# DA_CNNC.net
KiCad netlist of a schematic drawn in EasyEDA Pro
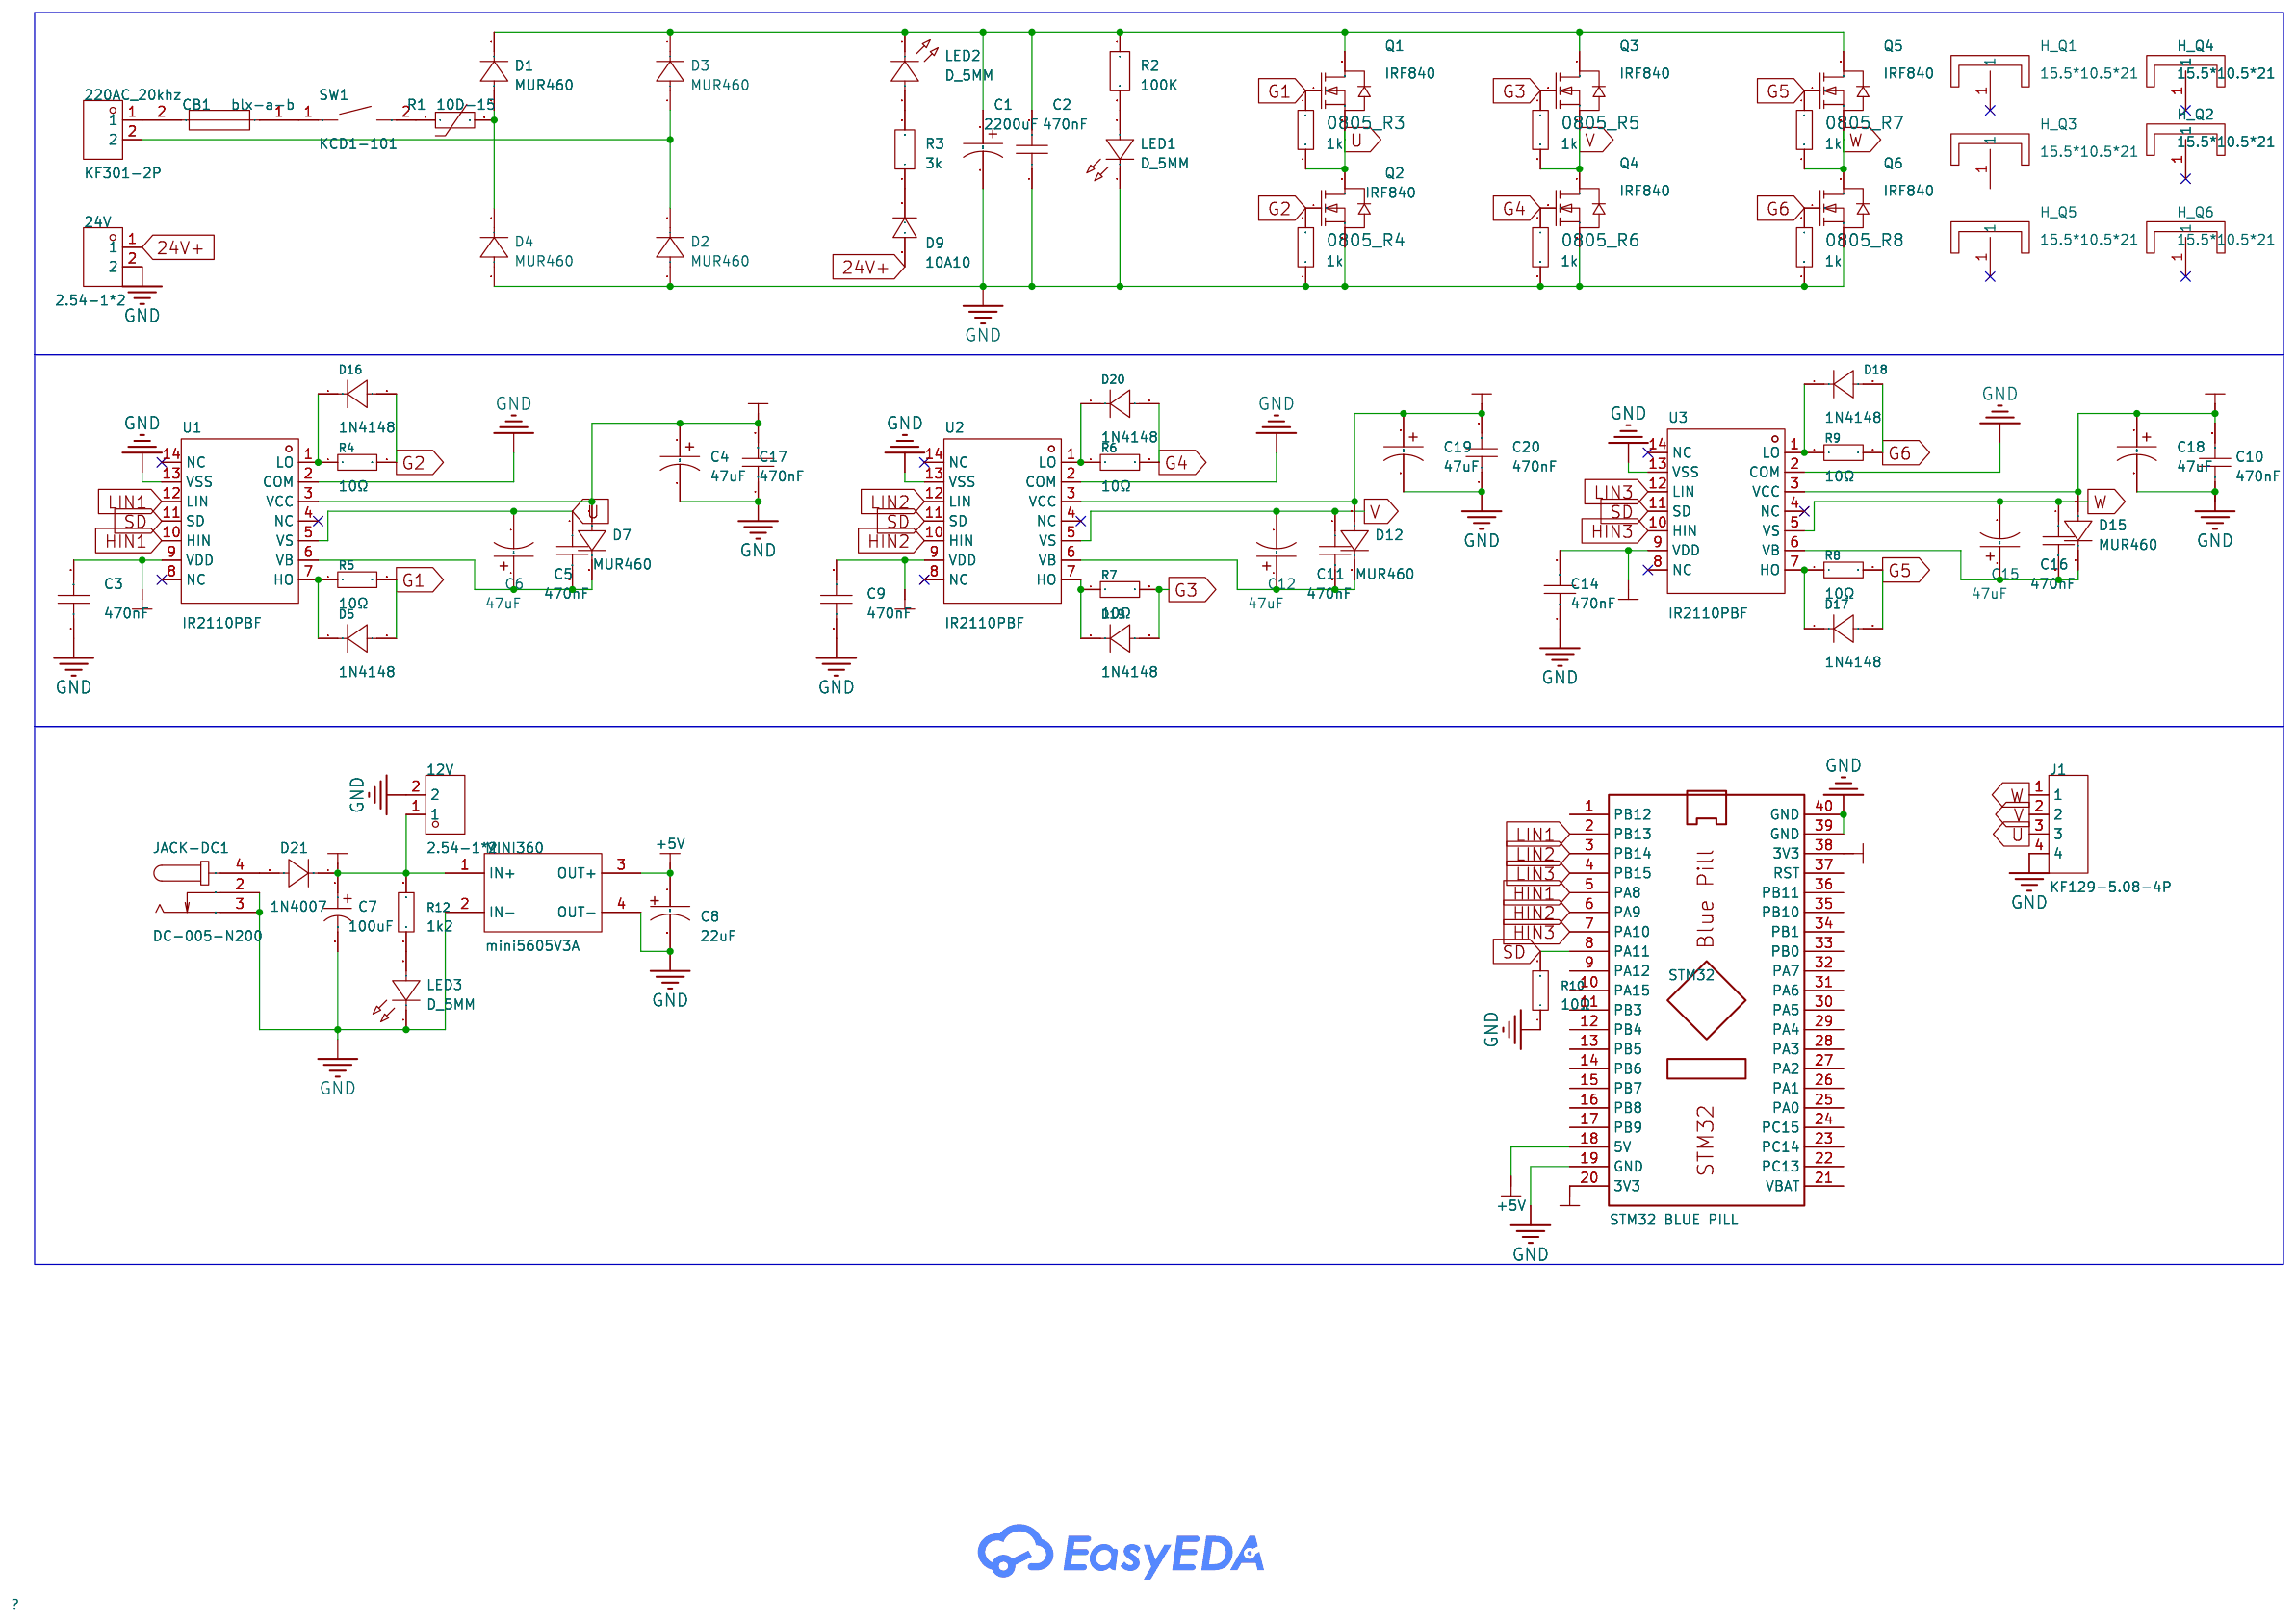
[diagram p0: schematic sheet]

(export (version "E")
  (design (tool "Eeschema 10.0.6"))
  (components
    (comp (ref "12V")
      (value "2.54-1*2")
      (footprint "easyedapro:HDR-TH_2P-P2.54-V-M")
      (fields (field (name "Manufacturer") "ZHOURI(洲日)"))
      (libsource (lib "easyedapro") (part "2.54-1*2"))
    )
    (comp (ref "24V")
      (value "2.54-1*2")
      (footprint "easyedapro:HDR-TH_2P-P2.54-V-M")
      (fields (field (name "Manufacturer") "ZHOURI(洲日)"))
      (libsource (lib "easyedapro") (part "2.54-1*2"))
    )
    (comp (ref "220AC_20khz")
      (value "KF301-2P")
      (footprint "easyedapro:CONN-TH_XY301V-A-5.0-2P")
      (libsource (lib "easyedapro") (part "KF301-2P接线端子"))
    )
    (comp (ref "0805_R3")
      (value "1k")
      (footprint "easyedapro:R0805")
      (fields
        (field (name "Manufacturer Part") "0805W8F1502T5E")
        (field (name "Manufacturer") "UNI-ROYAL(厚声)")
      )
      (libsource (lib "easyedapro") (part "0805W8F1502T5E"))
    )
    (comp (ref "0805_R4")
      (value "1k")
      (footprint "easyedapro:R0805")
      (fields
        (field (name "Manufacturer Part") "0805W8F1502T5E")
        (field (name "Manufacturer") "UNI-ROYAL(厚声)")
      )
      (libsource (lib "easyedapro") (part "0805W8F1502T5E"))
    )
    (comp (ref "0805_R5")
      (value "1k")
      (footprint "easyedapro:R0805")
      (fields
        (field (name "Manufacturer Part") "0805W8F1502T5E")
        (field (name "Manufacturer") "UNI-ROYAL(厚声)")
      )
      (libsource (lib "easyedapro") (part "0805W8F1502T5E"))
    )
    (comp (ref "0805_R6")
      (value "1k")
      (footprint "easyedapro:R0805")
      (fields
        (field (name "Manufacturer Part") "0805W8F1502T5E")
        (field (name "Manufacturer") "UNI-ROYAL(厚声)")
      )
      (libsource (lib "easyedapro") (part "0805W8F1502T5E"))
    )
    (comp (ref "0805_R7")
      (value "1k")
      (footprint "easyedapro:R0805")
      (fields
        (field (name "Manufacturer Part") "0805W8F1502T5E")
        (field (name "Manufacturer") "UNI-ROYAL(厚声)")
      )
      (libsource (lib "easyedapro") (part "0805W8F1502T5E"))
    )
    (comp (ref "0805_R8")
      (value "1k")
      (footprint "easyedapro:R0805")
      (fields
        (field (name "Manufacturer Part") "0805W8F1502T5E")
        (field (name "Manufacturer") "UNI-ROYAL(厚声)")
      )
      (libsource (lib "easyedapro") (part "0805W8F1502T5E"))
    )
    (comp (ref "C1")
      (value "2200uF")
      (footprint "easyedapro:CAP-TH_BD25.0-P10.00-D2.3-FD")
      (fields
        (field (name "Manufacturer Part") "450VXG220MEFCSN25X40")
        (field (name "Manufacturer") "Rubycon(红宝石)")
      )
      (libsource (lib "easyedapro") (part "450VXG220MEFCSN25X40"))
    )
    (comp (ref "C2")
      (value "470nF")
      (footprint "easyedapro:CAP-TH_L22.5-W7.5-P20.00-D1.2")
      (fields (field (name "Manufacturer Part") "KP474J2J2001") (field (name "Manufacturer") "KYET(科雅)"))
      (libsource (lib "easyedapro") (part "KP474J2J2001"))
    )
    (comp (ref "C3")
      (value "470nF")
      (footprint "easyedapro:C0805")
      (description "Capacitance:4.7pF Voltage Rating:100V Temperature Coefficient:NP0")
      (fields
        (field (name "Manufacturer Part") "CC0805CRNPO0BN4R7")
        (field (name "Manufacturer") "YAGEO(国巨)")
      )
      (libsource (lib "easyedapro") (part "CC0805CRNPO0BN4R7"))
    )
    (comp (ref "C4")
      (value "47uF")
      (footprint "easyedapro:CAP-TH_BD6.3-P2.5-D0.5")
      (fields (field (name "Manufacturer Part") "50V47uF CD288") (field (name "Manufacturer") "HRK(鸿瑞凯电子)"))
      (libsource (lib "easyedapro") (part "50V47UF CD288"))
    )
    (comp (ref "C5")
      (value "470nF")
      (footprint "easyedapro:C0805")
      (description "Capacitance:4.7pF Voltage Rating:100V Temperature Coefficient:NP0")
      (fields
        (field (name "Manufacturer Part") "CC0805CRNPO0BN4R7")
        (field (name "Manufacturer") "YAGEO(国巨)")
      )
      (libsource (lib "easyedapro") (part "CC0805CRNPO0BN4R7"))
    )
    (comp (ref "C6")
      (value "47uF")
      (footprint "easyedapro:CAP-TH_BD6.3-P2.5-D0.5")
      (fields (field (name "Manufacturer Part") "50V47uF CD288") (field (name "Manufacturer") "HRK(鸿瑞凯电子)"))
      (libsource (lib "easyedapro") (part "50V47UF CD288"))
    )
    (comp (ref "C7")
      (value "100uF")
      (footprint "easyedapro:CAP-TH_BD6.3-P2.50-D0.5-FD-100UF25V6.3X11KM")
      (fields
        (field (name "Manufacturer Part") "100uF25V6.3x11KM")
        (field (name "Manufacturer") "Econd(米朗电子)")
      )
      (libsource (lib "easyedapro") (part "100UF25V6.3X11KM"))
    )
    (comp (ref "C8")
      (value "22uF")
      (footprint "easyedapro:CAP-TH_BD4.0-P1.50-D0.8-FD")
      (fields (field (name "Manufacturer Part") "ECEA1CKA220") (field (name "Manufacturer") "PANASONIC(松下)"))
      (libsource (lib "easyedapro") (part "ECEA1CKA220"))
    )
    (comp (ref "C9")
      (value "470nF")
      (footprint "easyedapro:C0805")
      (description "Capacitance:4.7pF Voltage Rating:100V Temperature Coefficient:NP0")
      (fields
        (field (name "Manufacturer Part") "CC0805CRNPO0BN4R7")
        (field (name "Manufacturer") "YAGEO(国巨)")
      )
      (libsource (lib "easyedapro") (part "CC0805CRNPO0BN4R7"))
    )
    (comp (ref "C10")
      (value "470nF")
      (footprint "easyedapro:C0805")
      (description "Capacitance:4.7pF Voltage Rating:100V Temperature Coefficient:NP0")
      (fields
        (field (name "Manufacturer Part") "CC0805CRNPO0BN4R7")
        (field (name "Manufacturer") "YAGEO(国巨)")
      )
      (libsource (lib "easyedapro") (part "CC0805CRNPO0BN4R7"))
    )
    (comp (ref "C11")
      (value "470nF")
      (footprint "easyedapro:C0805")
      (description "Capacitance:4.7pF Voltage Rating:100V Temperature Coefficient:NP0")
      (fields
        (field (name "Manufacturer Part") "CC0805CRNPO0BN4R7")
        (field (name "Manufacturer") "YAGEO(国巨)")
      )
      (libsource (lib "easyedapro") (part "CC0805CRNPO0BN4R7"))
    )
    (comp (ref "C12")
      (value "47uF")
      (footprint "easyedapro:CAP-TH_BD6.3-P2.5-D0.5")
      (fields (field (name "Manufacturer Part") "50V47uF CD288") (field (name "Manufacturer") "HRK(鸿瑞凯电子)"))
      (libsource (lib "easyedapro") (part "50V47UF CD288"))
    )
    (comp (ref "C14")
      (value "470nF")
      (footprint "easyedapro:C0805")
      (description "Capacitance:4.7pF Voltage Rating:100V Temperature Coefficient:NP0")
      (fields
        (field (name "Manufacturer Part") "CC0805CRNPO0BN4R7")
        (field (name "Manufacturer") "YAGEO(国巨)")
      )
      (libsource (lib "easyedapro") (part "CC0805CRNPO0BN4R7"))
    )
    (comp (ref "C15")
      (value "47uF")
      (footprint "easyedapro:CAP-TH_BD6.3-P2.5-D0.5")
      (fields (field (name "Manufacturer Part") "50V47uF CD288") (field (name "Manufacturer") "HRK(鸿瑞凯电子)"))
      (libsource (lib "easyedapro") (part "50V47UF CD288"))
    )
    (comp (ref "C16")
      (value "470nF")
      (footprint "easyedapro:C0805")
      (description "Capacitance:4.7pF Voltage Rating:100V Temperature Coefficient:NP0")
      (fields
        (field (name "Manufacturer Part") "CC0805CRNPO0BN4R7")
        (field (name "Manufacturer") "YAGEO(国巨)")
      )
      (libsource (lib "easyedapro") (part "CC0805CRNPO0BN4R7"))
    )
    (comp (ref "C17")
      (value "470nF")
      (footprint "easyedapro:C0805")
      (description "Capacitance:4.7pF Voltage Rating:100V Temperature Coefficient:NP0")
      (fields
        (field (name "Manufacturer Part") "CC0805CRNPO0BN4R7")
        (field (name "Manufacturer") "YAGEO(国巨)")
      )
      (libsource (lib "easyedapro") (part "CC0805CRNPO0BN4R7"))
    )
    (comp (ref "C18")
      (value "47uF")
      (footprint "easyedapro:CAP-TH_BD6.3-P2.5-D0.5")
      (fields (field (name "Manufacturer Part") "50V47uF CD288") (field (name "Manufacturer") "HRK(鸿瑞凯电子)"))
      (libsource (lib "easyedapro") (part "50V47UF CD288"))
    )
    (comp (ref "C19")
      (value "47uF")
      (footprint "easyedapro:CAP-TH_BD6.3-P2.5-D0.5")
      (fields (field (name "Manufacturer Part") "50V47uF CD288") (field (name "Manufacturer") "HRK(鸿瑞凯电子)"))
      (libsource (lib "easyedapro") (part "50V47UF CD288"))
    )
    (comp (ref "C20")
      (value "470nF")
      (footprint "easyedapro:C0805")
      (description "Capacitance:4.7pF Voltage Rating:100V Temperature Coefficient:NP0")
      (fields
        (field (name "Manufacturer Part") "CC0805CRNPO0BN4R7")
        (field (name "Manufacturer") "YAGEO(国巨)")
      )
      (libsource (lib "easyedapro") (part "CC0805CRNPO0BN4R7"))
    )
    (comp (ref "CB1")
      (value "blx-a-b")
      (footprint "easyedapro:FUSE-TH_BLX-A-B")
      (description "Voltage Rating:500V Current Rating:10A")
      (fields (field (name "Manufacturer") "XFCN(兴飞)"))
      (libsource (lib "easyedapro") (part "BLX-A-B"))
    )
    (comp (ref "D1")
      (value "MUR460")
      (footprint "easyedapro:DO-201_BD5.1-L8.4-P15.24-D1.0-RD")
      (fields (field (name "Manufacturer") "GOOD-ARK(固锝)"))
      (libsource (lib "easyedapro") (part "MUR460_C2990844"))
    )
    (comp (ref "D2")
      (value "MUR460")
      (footprint "easyedapro:DO-201_BD5.1-L8.4-P15.24-D1.0-RD")
      (fields (field (name "Manufacturer") "GOOD-ARK(固锝)"))
      (libsource (lib "easyedapro") (part "MUR460_C2990844"))
    )
    (comp (ref "D3")
      (value "MUR460")
      (footprint "easyedapro:DO-201_BD5.1-L8.4-P15.24-D1.0-RD")
      (fields (field (name "Manufacturer") "GOOD-ARK(固锝)"))
      (libsource (lib "easyedapro") (part "MUR460_C2990844"))
    )
    (comp (ref "D4")
      (value "MUR460")
      (footprint "easyedapro:DO-201_BD5.1-L8.4-P15.24-D1.0-RD")
      (fields (field (name "Manufacturer") "GOOD-ARK(固锝)"))
      (libsource (lib "easyedapro") (part "MUR460_C2990844"))
    )
    (comp (ref "D5")
      (value "1N4148")
      (footprint "easyedapro:DO-35_BD2.0-L4.2-P8.20-D0.5-RD")
      (fields (field (name "Manufacturer") "SMC(桑德斯)"))
      (libsource (lib "easyedapro") (part "1N4148_C493188"))
    )
    (comp (ref "D7")
      (value "MUR460")
      (footprint "easyedapro:DO-201_BD5.1-L8.4-P15.24-D1.0-RD")
      (fields (field (name "Manufacturer") "GOOD-ARK(固锝)"))
      (libsource (lib "easyedapro") (part "MUR460_C2990844"))
    )
    (comp (ref "D9")
      (value "10A10")
      (footprint "easyedapro:R-6_BD8.9-L8.9-P12.90-D1.4-RD")
      (libsource (lib "easyedapro") (part "10A10_C132146"))
    )
    (comp (ref "D12")
      (value "MUR460")
      (footprint "easyedapro:DO-201_BD5.1-L8.4-P15.24-D1.0-RD")
      (fields (field (name "Manufacturer") "GOOD-ARK(固锝)"))
      (libsource (lib "easyedapro") (part "MUR460_C2990844"))
    )
    (comp (ref "D15")
      (value "MUR460")
      (footprint "easyedapro:DO-201_BD5.1-L8.4-P15.24-D1.0-RD")
      (fields (field (name "Manufacturer") "GOOD-ARK(固锝)"))
      (libsource (lib "easyedapro") (part "MUR460_C2990844"))
    )
    (comp (ref "D16")
      (value "1N4148")
      (footprint "easyedapro:DO-35_BD2.0-L4.2-P8.20-D0.5-RD")
      (fields (field (name "Manufacturer") "SMC(桑德斯)"))
      (libsource (lib "easyedapro") (part "1N4148_C493188"))
    )
    (comp (ref "D17")
      (value "1N4148")
      (footprint "easyedapro:DO-35_BD2.0-L4.2-P8.20-D0.5-RD")
      (fields (field (name "Manufacturer") "SMC(桑德斯)"))
      (libsource (lib "easyedapro") (part "1N4148_C493188"))
    )
    (comp (ref "D18")
      (value "1N4148")
      (footprint "easyedapro:DO-35_BD2.0-L4.2-P8.20-D0.5-RD")
      (fields (field (name "Manufacturer") "SMC(桑德斯)"))
      (libsource (lib "easyedapro") (part "1N4148_C493188"))
    )
    (comp (ref "D19")
      (value "1N4148")
      (footprint "easyedapro:DO-35_BD2.0-L4.2-P8.20-D0.5-RD")
      (fields (field (name "Manufacturer") "SMC(桑德斯)"))
      (libsource (lib "easyedapro") (part "1N4148_C493188"))
    )
    (comp (ref "D20")
      (value "1N4148")
      (footprint "easyedapro:DO-35_BD2.0-L4.2-P8.20-D0.5-RD")
      (fields (field (name "Manufacturer") "SMC(桑德斯)"))
      (libsource (lib "easyedapro") (part "1N4148_C493188"))
    )
    (comp (ref "D21")
      (value "1N4007")
      (footprint "easyedapro:DO-41_BD2.4-L4.7-P8.70-D0.8-RD")
      (fields (field (name "Manufacturer") "baocheng(宝乘)"))
      (libsource (lib "easyedapro") (part "1N4007_C47018538"))
    )
    (comp (ref "H_Q1")
      (value "15.5*10.5*21")
      (footprint "easyedapro:SINK-TH_L15.0-W10.5-H21.0")
      (fields (field (name "Manufacturer") "XSD(鑫顺达)"))
      (libsource (lib "easyedapro") (part "15*10.5*21"))
    )
    (comp (ref "H_Q2")
      (value "15.5*10.5*21")
      (footprint "easyedapro:SINK-TH_L15.0-W10.5-H21.0")
      (fields (field (name "Manufacturer") "XSD(鑫顺达)"))
      (libsource (lib "easyedapro") (part "15*10.5*21"))
    )
    (comp (ref "H_Q3")
      (value "15.5*10.5*21")
      (footprint "easyedapro:SINK-TH_L15.0-W10.5-H21.0")
      (fields (field (name "Manufacturer") "XSD(鑫顺达)"))
      (libsource (lib "easyedapro") (part "15*10.5*21"))
    )
    (comp (ref "H_Q4")
      (value "15.5*10.5*21")
      (footprint "easyedapro:SINK-TH_L15.0-W10.5-H21.0")
      (fields (field (name "Manufacturer") "XSD(鑫顺达)"))
      (libsource (lib "easyedapro") (part "15*10.5*21"))
    )
    (comp (ref "H_Q5")
      (value "15.5*10.5*21")
      (footprint "easyedapro:SINK-TH_L15.0-W10.5-H21.0")
      (fields (field (name "Manufacturer") "XSD(鑫顺达)"))
      (libsource (lib "easyedapro") (part "15*10.5*21"))
    )
    (comp (ref "H_Q6")
      (value "15.5*10.5*21")
      (footprint "easyedapro:SINK-TH_L15.0-W10.5-H21.0")
      (fields (field (name "Manufacturer") "XSD(鑫顺达)"))
      (libsource (lib "easyedapro") (part "15*10.5*21"))
    )
    (comp (ref "J1")
      (value "KF129-5.08-4P")
      (footprint "easyedapro:CONN-TH_4P-P5.08_KF129-5.08-4P")
      (libsource (lib "easyedapro") (part "KF129-5.08-4P"))
    )
    (comp (ref "JACK-DC1")
      (value "DC-005-N200")
      (footprint "easyedapro:DC-IN-TH_DC-005-N200")
      (fields (field (name "Manufacturer") "HANBO(汉博)"))
      (libsource (lib "easyedapro") (part "DC-005-N200"))
    )
    (comp (ref "LED1")
      (value "D_5MM")
      (footprint "easyedapro:LED-TH_BD5.0-P2.54-L-RD_GREEN")
      (libsource (lib "easyedapro") (part "草帽LED绿灯"))
    )
    (comp (ref "LED2")
      (value "D_5MM")
      (footprint "easyedapro:LED-TH_BD5.0-P2.54-L-RD_GREEN")
      (libsource (lib "easyedapro") (part "草帽LED绿灯"))
    )
    (comp (ref "LED3")
      (value "D_5MM")
      (footprint "easyedapro:LED-TH_BD5.0-P2.54-L-RD_GREEN")
      (libsource (lib "easyedapro") (part "草帽LED绿灯"))
    )
    (comp (ref "MINI360")
      (value "mini5605V3A")
      (footprint "easyedapro:COMM-SMD_MINI5605V5A")
      (libsource (lib "easyedapro") (part "MINI5605V5A输出电源模块"))
    )
    (comp (ref "Q1")
      (value "IRF840")
      (footprint "easyedapro:TO-220-3_L10.2-W4.5-P2.54-L-1")
      (fields (field (name "Manufacturer") "minos(迈诺斯)"))
      (libsource (lib "easyedapro") (part "IRF840_C2980294"))
    )
    (comp (ref "Q2")
      (value "IRF840")
      (footprint "easyedapro:TO-220-3_L10.2-W4.5-P2.54-L-1")
      (fields (field (name "Manufacturer") "minos(迈诺斯)"))
      (libsource (lib "easyedapro") (part "IRF840_C2980294"))
    )
    (comp (ref "Q3")
      (value "IRF840")
      (footprint "easyedapro:TO-220-3_L10.2-W4.5-P2.54-L-1")
      (fields (field (name "Manufacturer") "minos(迈诺斯)"))
      (libsource (lib "easyedapro") (part "IRF840_C2980294"))
    )
    (comp (ref "Q4")
      (value "IRF840")
      (footprint "easyedapro:TO-220-3_L10.2-W4.5-P2.54-L-1")
      (fields (field (name "Manufacturer") "minos(迈诺斯)"))
      (libsource (lib "easyedapro") (part "IRF840_C2980294"))
    )
    (comp (ref "Q5")
      (value "IRF840")
      (footprint "easyedapro:TO-220-3_L10.2-W4.5-P2.54-L-1")
      (fields (field (name "Manufacturer") "minos(迈诺斯)"))
      (libsource (lib "easyedapro") (part "IRF840_C2980294"))
    )
    (comp (ref "Q6")
      (value "IRF840")
      (footprint "easyedapro:TO-220-3_L10.2-W4.5-P2.54-L-1")
      (fields (field (name "Manufacturer") "minos(迈诺斯)"))
      (libsource (lib "easyedapro") (part "IRF840_C2980294"))
    )
    (comp (ref "R1")
      (value "10D-15")
      (footprint "easyedapro:RES-TH_L17.5-W6.0-P7.50-D0.8-S7.50")
      (fields (field (name "Manufacturer") "SURGING(绍鑫)"))
      (libsource (lib "easyedapro") (part "10D-15"))
    )
    (comp (ref "R2")
      (value "100K")
      (footprint "easyedapro:RES-TH_L22.0-W10.0-P26.00-D1.0")
      (fields (field (name "Manufacturer Part") "SQP5W-3Ω±5%-9P") (field (name "Manufacturer") "VO(翔胜)"))
      (libsource (lib "easyedapro") (part "SQP5W-3Ω±5%-9P"))
    )
    (comp (ref "R3")
      (value "3k")
      (footprint "easyedapro:RES-TH_BD2.4-L6.3-P10.30-D0.6")
      (fields
        (field (name "Manufacturer Part") "RD 1/4W 220R J T/B A1")
        (field (name "Manufacturer") "Tyohm(幸亚电阻)")
      )
      (libsource (lib "easyedapro") (part "RD 1/4W 220R J T/B A1"))
    )
    (comp (ref "R4")
      (value "10Ω")
      (footprint "easyedapro:R1206")
      (fields
        (field (name "Manufacturer Part") "1206W4F100KT5E")
        (field (name "Manufacturer") "UNI-ROYAL(厚声)")
      )
      (libsource (lib "easyedapro") (part "1206W4F100KT5E"))
    )
    (comp (ref "R5")
      (value "10Ω")
      (footprint "easyedapro:R1206")
      (fields
        (field (name "Manufacturer Part") "1206W4F100KT5E")
        (field (name "Manufacturer") "UNI-ROYAL(厚声)")
      )
      (libsource (lib "easyedapro") (part "1206W4F100KT5E"))
    )
    (comp (ref "R6")
      (value "10Ω")
      (footprint "easyedapro:R1206")
      (fields
        (field (name "Manufacturer Part") "1206W4F100KT5E")
        (field (name "Manufacturer") "UNI-ROYAL(厚声)")
      )
      (libsource (lib "easyedapro") (part "1206W4F100KT5E"))
    )
    (comp (ref "R7")
      (value "10Ω")
      (footprint "easyedapro:R1206")
      (fields
        (field (name "Manufacturer Part") "1206W4F100KT5E")
        (field (name "Manufacturer") "UNI-ROYAL(厚声)")
      )
      (libsource (lib "easyedapro") (part "1206W4F100KT5E"))
    )
    (comp (ref "R8")
      (value "10Ω")
      (footprint "easyedapro:R1206")
      (fields
        (field (name "Manufacturer Part") "1206W4F100KT5E")
        (field (name "Manufacturer") "UNI-ROYAL(厚声)")
      )
      (libsource (lib "easyedapro") (part "1206W4F100KT5E"))
    )
    (comp (ref "R9")
      (value "10Ω")
      (footprint "easyedapro:R1206")
      (fields
        (field (name "Manufacturer Part") "1206W4F100KT5E")
        (field (name "Manufacturer") "UNI-ROYAL(厚声)")
      )
      (libsource (lib "easyedapro") (part "1206W4F100KT5E"))
    )
    (comp (ref "R10")
      (value "10Ω")
      (footprint "easyedapro:R1206")
      (fields
        (field (name "Manufacturer Part") "1206W4F100KT5E")
        (field (name "Manufacturer") "UNI-ROYAL(厚声)")
      )
      (libsource (lib "easyedapro") (part "1206W4F100KT5E"))
    )
    (comp (ref "R12")
      (value "10Ω")
      (footprint "easyedapro:R1206")
      (fields
        (field (name "Manufacturer Part") "1206W4F100KT5E")
        (field (name "Manufacturer") "UNI-ROYAL(厚声)")
      )
      (libsource (lib "easyedapro") (part "1206W4F100KT5E"))
    )
    (comp (ref "STM32")
      (value "STM32 BLUE PILL")
      (footprint "easyedapro:STM32F103C8T6 BLUE PILL")
      (libsource (lib "easyedapro") (part "STM32 BLUE PILL"))
    )
    (comp (ref "SW1")
      (value "KCD1-101")
      (footprint "easyedapro:SW-TH_KCD1-101")
      (libsource (lib "easyedapro") (part "KCD1-101_C9900022451"))
    )
    (comp (ref "U1")
      (value "IR2110PBF")
      (footprint "easyedapro:DIP-14_L20.0-W7.6-P2.54-LS7.6-BL")
      (fields (field (name "Manufacturer") "Infineon(英飞凌)"))
      (libsource (lib "easyedapro") (part "IR2110PBF_C2967"))
    )
    (comp (ref "U2")
      (value "IR2110PBF")
      (footprint "easyedapro:DIP-14_L20.0-W7.6-P2.54-LS7.6-BL")
      (fields (field (name "Manufacturer") "Infineon(英飞凌)"))
      (libsource (lib "easyedapro") (part "IR2110PBF_C2967"))
    )
    (comp (ref "U3")
      (value "IR2110PBF")
      (footprint "easyedapro:DIP-14_L20.0-W7.6-P2.54-LS7.6-BL")
      (fields (field (name "Manufacturer") "Infineon(英飞凌)"))
      (libsource (lib "easyedapro") (part "IR2110PBF_C2967"))
    )
  )
  (nets
    (net (code "1") (name "+3.3V") (class "Default")
      (node (ref "C14") (pin "2") (pinfunction "2_2") (pintype "unspecified"))
      (node (ref "C3") (pin "2") (pinfunction "2_2") (pintype "unspecified"))
      (node (ref "C9") (pin "2") (pinfunction "2_2") (pintype "unspecified"))
      (node (ref "STM32") (pin "20") (pinfunction "3V3_20") (pintype "unspecified"))
      (node (ref "STM32") (pin "38") (pinfunction "3V3_38") (pintype "unspecified"))
      (node (ref "U1") (pin "9") (pinfunction "VDD_9") (pintype "unspecified"))
      (node (ref "U2") (pin "9") (pinfunction "VDD_9") (pintype "unspecified"))
      (node (ref "U3") (pin "9") (pinfunction "VDD_9") (pintype "unspecified"))
    )
    (net (code "2") (name "+5V") (class "Default")
      (node (ref "C8") (pin "1") (pinfunction "1_1") (pintype "input"))
      (node (ref "MINI360") (pin "3") (pinfunction "OUT+_3") (pintype "unspecified"))
      (node (ref "STM32") (pin "18") (pinfunction "5V_18") (pintype "unspecified"))
    )
    (net (code "3") (name "+12V") (class "Default")
      (node (ref "12V") (pin "1") (pinfunction "1_1") (pintype "unspecified"))
      (node (ref "C10") (pin "2") (pinfunction "2_2") (pintype "unspecified"))
      (node (ref "C17") (pin "2") (pinfunction "2_2") (pintype "unspecified"))
      (node (ref "C18") (pin "1") (pinfunction "1_1") (pintype "unspecified"))
      (node (ref "C19") (pin "1") (pinfunction "1_1") (pintype "unspecified"))
      (node (ref "C20") (pin "2") (pinfunction "2_2") (pintype "unspecified"))
      (node (ref "C4") (pin "1") (pinfunction "1_1") (pintype "unspecified"))
      (node (ref "C7") (pin "1") (pinfunction "1_1") (pintype "input"))
      (node (ref "D12") (pin "2") (pinfunction "A_2") (pintype "unspecified"))
      (node (ref "D15") (pin "2") (pinfunction "A_2") (pintype "unspecified"))
      (node (ref "D21") (pin "1") (pinfunction "C_1") (pintype "unspecified"))
      (node (ref "D7") (pin "2") (pinfunction "A_2") (pintype "unspecified"))
      (node (ref "MINI360") (pin "1") (pinfunction "IN+_1") (pintype "unspecified"))
      (node (ref "R12") (pin "2") (pinfunction "2_2") (pintype "input"))
      (node (ref "U1") (pin "3") (pinfunction "VCC_3") (pintype "unspecified"))
      (node (ref "U2") (pin "3") (pinfunction "VCC_3") (pintype "unspecified"))
      (node (ref "U3") (pin "3") (pinfunction "VCC_3") (pintype "unspecified"))
    )
    (net (code "4") (name "24V+") (class "Default")
      (node (ref "24V") (pin "1") (pinfunction "1_1") (pintype "unspecified"))
      (node (ref "D9") (pin "2") (pinfunction "A_2") (pintype "unspecified"))
    )
    (net (code "5") (name "G1") (class "Default")
      (node (ref "0805_R3") (pin "1") (pinfunction "1_1") (pintype "input"))
      (node (ref "D5") (pin "2") (pinfunction "A_2") (pintype "input"))
      (node (ref "Q1") (pin "1") (pinfunction "G_1") (pintype "unspecified"))
      (node (ref "R5") (pin "2") (pinfunction "2_2") (pintype "input"))
    )
    (net (code "6") (name "G2") (class "Default")
      (node (ref "0805_R4") (pin "2") (pinfunction "2_2") (pintype "input"))
      (node (ref "D16") (pin "2") (pinfunction "A_2") (pintype "input"))
      (node (ref "Q2") (pin "1") (pinfunction "G_1") (pintype "unspecified"))
      (node (ref "R4") (pin "2") (pinfunction "2_2") (pintype "input"))
    )
    (net (code "7") (name "G3") (class "Default")
      (node (ref "0805_R5") (pin "1") (pinfunction "1_1") (pintype "input"))
      (node (ref "D19") (pin "2") (pinfunction "A_2") (pintype "input"))
      (node (ref "Q3") (pin "1") (pinfunction "G_1") (pintype "unspecified"))
      (node (ref "R7") (pin "2") (pinfunction "2_2") (pintype "input"))
    )
    (net (code "8") (name "G4") (class "Default")
      (node (ref "0805_R6") (pin "1") (pinfunction "1_1") (pintype "input"))
      (node (ref "D20") (pin "2") (pinfunction "A_2") (pintype "input"))
      (node (ref "Q4") (pin "1") (pinfunction "G_1") (pintype "unspecified"))
      (node (ref "R6") (pin "2") (pinfunction "2_2") (pintype "input"))
    )
    (net (code "9") (name "G5") (class "Default")
      (node (ref "0805_R7") (pin "1") (pinfunction "1_1") (pintype "input"))
      (node (ref "D17") (pin "2") (pinfunction "A_2") (pintype "input"))
      (node (ref "Q5") (pin "1") (pinfunction "G_1") (pintype "unspecified"))
      (node (ref "R8") (pin "2") (pinfunction "2_2") (pintype "input"))
    )
    (net (code "10") (name "G6") (class "Default")
      (node (ref "0805_R8") (pin "1") (pinfunction "1_1") (pintype "input"))
      (node (ref "D18") (pin "2") (pinfunction "A_2") (pintype "input"))
      (node (ref "Q6") (pin "1") (pinfunction "G_1") (pintype "unspecified"))
      (node (ref "R9") (pin "2") (pinfunction "2_2") (pintype "input"))
    )
    (net (code "11") (name "GND") (class "Default")
      (node (ref "0805_R4") (pin "1") (pinfunction "1_1") (pintype "input"))
      (node (ref "0805_R6") (pin "2") (pinfunction "2_2") (pintype "input"))
      (node (ref "0805_R8") (pin "2") (pinfunction "2_2") (pintype "input"))
      (node (ref "12V") (pin "2") (pinfunction "2_2") (pintype "unspecified"))
      (node (ref "24V") (pin "2") (pinfunction "2_2") (pintype "unspecified"))
      (node (ref "C1") (pin "2") (pinfunction "2_2") (pintype "unspecified"))
      (node (ref "C10") (pin "1") (pinfunction "1_1") (pintype "unspecified"))
      (node (ref "C14") (pin "1") (pinfunction "1_1") (pintype "unspecified"))
      (node (ref "C17") (pin "1") (pinfunction "1_1") (pintype "unspecified"))
      (node (ref "C18") (pin "2") (pinfunction "2_2") (pintype "unspecified"))
      (node (ref "C19") (pin "2") (pinfunction "2_2") (pintype "unspecified"))
      (node (ref "C2") (pin "1") (pinfunction "1_1") (pintype "input"))
      (node (ref "C20") (pin "1") (pinfunction "1_1") (pintype "unspecified"))
      (node (ref "C3") (pin "1") (pinfunction "1_1") (pintype "unspecified"))
      (node (ref "C4") (pin "2") (pinfunction "2_2") (pintype "unspecified"))
      (node (ref "C7") (pin "2") (pinfunction "2_2") (pintype "input"))
      (node (ref "C8") (pin "2") (pinfunction "2_2") (pintype "input"))
      (node (ref "C9") (pin "1") (pinfunction "1_1") (pintype "unspecified"))
      (node (ref "D2") (pin "2") (pinfunction "A_2") (pintype "unspecified"))
      (node (ref "D4") (pin "2") (pinfunction "A_2") (pintype "unspecified"))
      (node (ref "J1") (pin "4") (pinfunction "4_4") (pintype "unspecified"))
      (node (ref "JACK-DC1") (pin "2") (pinfunction "2_2") (pintype "unspecified"))
      (node (ref "JACK-DC1") (pin "3") (pinfunction "3_3") (pintype "unspecified"))
      (node (ref "LED1") (pin "1") (pinfunction "K_1") (pintype "unspecified"))
      (node (ref "LED3") (pin "1") (pinfunction "K_1") (pintype "unspecified"))
      (node (ref "MINI360") (pin "2") (pinfunction "IN-_2") (pintype "unspecified"))
      (node (ref "MINI360") (pin "4") (pinfunction "OUT-_4") (pintype "unspecified"))
      (node (ref "Q2") (pin "3") (pinfunction "S_3") (pintype "unspecified"))
      (node (ref "Q4") (pin "3") (pinfunction "S_3") (pintype "unspecified"))
      (node (ref "Q6") (pin "3") (pinfunction "S_3") (pintype "unspecified"))
      (node (ref "R10") (pin "1") (pinfunction "1_1") (pintype "input"))
      (node (ref "STM32") (pin "19") (pinfunction "GND_19") (pintype "unspecified"))
      (node (ref "STM32") (pin "39") (pinfunction "GND_39") (pintype "unspecified"))
      (node (ref "STM32") (pin "40") (pinfunction "GND_40") (pintype "unspecified"))
      (node (ref "U1") (pin "13") (pinfunction "VSS_13") (pintype "unspecified"))
      (node (ref "U1") (pin "2") (pinfunction "COM_2") (pintype "unspecified"))
      (node (ref "U2") (pin "13") (pinfunction "VSS_13") (pintype "unspecified"))
      (node (ref "U2") (pin "2") (pinfunction "COM_2") (pintype "unspecified"))
      (node (ref "U3") (pin "13") (pinfunction "VSS_13") (pintype "unspecified"))
      (node (ref "U3") (pin "2") (pinfunction "COM_2") (pintype "unspecified"))
    )
    (net (code "12") (name "HIN1") (class "Default")
      (node (ref "STM32") (pin "5") (pinfunction "PA8_5") (pintype "unspecified"))
      (node (ref "U1") (pin "10") (pinfunction "HIN_10") (pintype "unspecified"))
    )
    (net (code "13") (name "HIN2") (class "Default")
      (node (ref "STM32") (pin "6") (pinfunction "PA9_6") (pintype "unspecified"))
      (node (ref "U2") (pin "10") (pinfunction "HIN_10") (pintype "unspecified"))
    )
    (net (code "14") (name "HIN3") (class "Default")
      (node (ref "STM32") (pin "7") (pinfunction "PA10_7") (pintype "unspecified"))
      (node (ref "U3") (pin "10") (pinfunction "HIN_10") (pintype "unspecified"))
    )
    (net (code "15") (name "LIN1") (class "Default")
      (node (ref "STM32") (pin "2") (pinfunction "PB13_2") (pintype "unspecified"))
      (node (ref "U1") (pin "12") (pinfunction "LIN_12") (pintype "unspecified"))
    )
    (net (code "16") (name "LIN2") (class "Default")
      (node (ref "STM32") (pin "3") (pinfunction "PB14_3") (pintype "unspecified"))
      (node (ref "U2") (pin "12") (pinfunction "LIN_12") (pintype "unspecified"))
    )
    (net (code "17") (name "LIN3") (class "Default")
      (node (ref "STM32") (pin "4") (pinfunction "PB15_4") (pintype "unspecified"))
      (node (ref "U3") (pin "12") (pinfunction "LIN_12") (pintype "unspecified"))
    )
    (net (code "18") (name "Net-(220AC_20khz-Pad1)") (class "Default")
      (node (ref "220AC_20khz") (pin "1") (pinfunction "1_1") (pintype "unspecified"))
      (node (ref "CB1") (pin "2") (pinfunction "2_2") (pintype "unspecified"))
    )
    (net (code "19") (name "Net-(CB1-Pad1)") (class "Default")
      (node (ref "CB1") (pin "1") (pinfunction "1_1") (pintype "unspecified"))
      (node (ref "SW1") (pin "1") (pinfunction "1_1") (pintype "input"))
    )
    (net (code "20") (name "Net-(D1-A)") (class "Default")
      (node (ref "D1") (pin "2") (pinfunction "A_2") (pintype "unspecified"))
      (node (ref "D4") (pin "1") (pinfunction "K_1") (pintype "unspecified"))
      (node (ref "R1") (pin "2") (pinfunction "2_2") (pintype "unspecified"))
    )
    (net (code "21") (name "Net-(D1-K)") (class "Default")
      (node (ref "C1") (pin "1") (pinfunction "1_1") (pintype "unspecified"))
      (node (ref "C2") (pin "2") (pinfunction "2_2") (pintype "input"))
      (node (ref "D1") (pin "1") (pinfunction "K_1") (pintype "unspecified"))
      (node (ref "D3") (pin "1") (pinfunction "K_1") (pintype "unspecified"))
      (node (ref "LED2") (pin "1") (pinfunction "K_1") (pintype "unspecified"))
      (node (ref "Q1") (pin "2") (pinfunction "D_2") (pintype "unspecified"))
      (node (ref "Q3") (pin "2") (pinfunction "D_2") (pintype "unspecified"))
      (node (ref "Q5") (pin "2") (pinfunction "D_2") (pintype "unspecified"))
      (node (ref "R2") (pin "1") (pinfunction "1_1") (pintype "unspecified"))
    )
    (net (code "22") (name "Net-(D2-K)") (class "Default")
      (node (ref "220AC_20khz") (pin "2") (pinfunction "2_2") (pintype "unspecified"))
      (node (ref "D2") (pin "1") (pinfunction "K_1") (pintype "unspecified"))
      (node (ref "D3") (pin "2") (pinfunction "A_2") (pintype "unspecified"))
    )
    (net (code "23") (name "Net-(D5-K)") (class "Default")
      (node (ref "D5") (pin "1") (pinfunction "K_1") (pintype "input"))
      (node (ref "R5") (pin "1") (pinfunction "1_1") (pintype "input"))
      (node (ref "U1") (pin "7") (pinfunction "HO_7") (pintype "unspecified"))
    )
    (net (code "24") (name "Net-(D7-K)") (class "Default")
      (node (ref "C5") (pin "2") (pinfunction "2_2") (pintype "unspecified"))
      (node (ref "C6") (pin "1") (pinfunction "1_1") (pintype "unspecified"))
      (node (ref "D7") (pin "1") (pinfunction "K_1") (pintype "unspecified"))
      (node (ref "U1") (pin "6") (pinfunction "VB_6") (pintype "unspecified"))
    )
    (net (code "25") (name "Net-(D9-K)") (class "Default")
      (node (ref "D9") (pin "1") (pinfunction "K_1") (pintype "unspecified"))
      (node (ref "R3") (pin "1") (pinfunction "1_1") (pintype "unspecified"))
    )
    (net (code "26") (name "Net-(D12-K)") (class "Default")
      (node (ref "C11") (pin "2") (pinfunction "2_2") (pintype "unspecified"))
      (node (ref "C12") (pin "1") (pinfunction "1_1") (pintype "unspecified"))
      (node (ref "D12") (pin "1") (pinfunction "K_1") (pintype "unspecified"))
      (node (ref "U2") (pin "6") (pinfunction "VB_6") (pintype "unspecified"))
    )
    (net (code "27") (name "Net-(D15-K)") (class "Default")
      (node (ref "C15") (pin "1") (pinfunction "1_1") (pintype "unspecified"))
      (node (ref "C16") (pin "2") (pinfunction "2_2") (pintype "unspecified"))
      (node (ref "D15") (pin "1") (pinfunction "K_1") (pintype "unspecified"))
      (node (ref "U3") (pin "6") (pinfunction "VB_6") (pintype "unspecified"))
    )
    (net (code "28") (name "Net-(D16-K)") (class "Default")
      (node (ref "D16") (pin "1") (pinfunction "K_1") (pintype "input"))
      (node (ref "R4") (pin "1") (pinfunction "1_1") (pintype "input"))
      (node (ref "U1") (pin "1") (pinfunction "LO_1") (pintype "unspecified"))
    )
    (net (code "29") (name "Net-(D17-K)") (class "Default")
      (node (ref "D17") (pin "1") (pinfunction "K_1") (pintype "input"))
      (node (ref "R8") (pin "1") (pinfunction "1_1") (pintype "input"))
      (node (ref "U3") (pin "7") (pinfunction "HO_7") (pintype "unspecified"))
    )
    (net (code "30") (name "Net-(D18-K)") (class "Default")
      (node (ref "D18") (pin "1") (pinfunction "K_1") (pintype "input"))
      (node (ref "R9") (pin "1") (pinfunction "1_1") (pintype "input"))
      (node (ref "U3") (pin "1") (pinfunction "LO_1") (pintype "unspecified"))
    )
    (net (code "31") (name "Net-(D19-K)") (class "Default")
      (node (ref "D19") (pin "1") (pinfunction "K_1") (pintype "input"))
      (node (ref "R7") (pin "1") (pinfunction "1_1") (pintype "input"))
      (node (ref "U2") (pin "7") (pinfunction "HO_7") (pintype "unspecified"))
    )
    (net (code "32") (name "Net-(D20-K)") (class "Default")
      (node (ref "D20") (pin "1") (pinfunction "K_1") (pintype "input"))
      (node (ref "R6") (pin "1") (pinfunction "1_1") (pintype "input"))
      (node (ref "U2") (pin "1") (pinfunction "LO_1") (pintype "unspecified"))
    )
    (net (code "33") (name "Net-(D21-A)") (class "Default")
      (node (ref "D21") (pin "2") (pinfunction "A_2") (pintype "unspecified"))
      (node (ref "JACK-DC1") (pin "4") (pinfunction "4_4") (pintype "unspecified"))
    )
    (net (code "34") (name "Net-(LED1-A)") (class "Default")
      (node (ref "LED1") (pin "2") (pinfunction "A_2") (pintype "unspecified"))
      (node (ref "R2") (pin "2") (pinfunction "2_2") (pintype "unspecified"))
    )
    (net (code "35") (name "Net-(LED2-A)") (class "Default")
      (node (ref "LED2") (pin "2") (pinfunction "A_2") (pintype "unspecified"))
      (node (ref "R3") (pin "2") (pinfunction "2_2") (pintype "unspecified"))
    )
    (net (code "36") (name "Net-(LED3-A)") (class "Default")
      (node (ref "LED3") (pin "2") (pinfunction "A_2") (pintype "unspecified"))
      (node (ref "R12") (pin "1") (pinfunction "1_1") (pintype "input"))
    )
    (net (code "37") (name "Net-(R1-Pad1)") (class "Default")
      (node (ref "R1") (pin "1") (pinfunction "1_1") (pintype "unspecified"))
      (node (ref "SW1") (pin "2") (pinfunction "2_2") (pintype "input"))
    )
    (net (code "38") (name "SD") (class "Default")
      (node (ref "R10") (pin "2") (pinfunction "2_2") (pintype "input"))
      (node (ref "STM32") (pin "8") (pinfunction "PA11_8") (pintype "unspecified"))
      (node (ref "U1") (pin "11") (pinfunction "SD_11") (pintype "unspecified"))
      (node (ref "U2") (pin "11") (pinfunction "SD_11") (pintype "unspecified"))
      (node (ref "U3") (pin "11") (pinfunction "SD_11") (pintype "unspecified"))
    )
    (net (code "39") (name "U") (class "Default")
      (node (ref "0805_R3") (pin "2") (pinfunction "2_2") (pintype "input"))
      (node (ref "C5") (pin "1") (pinfunction "1_1") (pintype "unspecified"))
      (node (ref "C6") (pin "2") (pinfunction "2_2") (pintype "unspecified"))
      (node (ref "J1") (pin "3") (pinfunction "3_3") (pintype "unspecified"))
      (node (ref "Q1") (pin "3") (pinfunction "S_3") (pintype "unspecified"))
      (node (ref "Q2") (pin "2") (pinfunction "D_2") (pintype "unspecified"))
      (node (ref "U1") (pin "5") (pinfunction "VS_5") (pintype "unspecified"))
    )
    (net (code "40") (name "V") (class "Default")
      (node (ref "0805_R5") (pin "2") (pinfunction "2_2") (pintype "input"))
      (node (ref "C11") (pin "1") (pinfunction "1_1") (pintype "unspecified"))
      (node (ref "C12") (pin "2") (pinfunction "2_2") (pintype "unspecified"))
      (node (ref "J1") (pin "2") (pinfunction "2_2") (pintype "unspecified"))
      (node (ref "Q3") (pin "3") (pinfunction "S_3") (pintype "unspecified"))
      (node (ref "Q4") (pin "2") (pinfunction "D_2") (pintype "unspecified"))
      (node (ref "U2") (pin "5") (pinfunction "VS_5") (pintype "unspecified"))
    )
    (net (code "41") (name "W") (class "Default")
      (node (ref "0805_R7") (pin "2") (pinfunction "2_2") (pintype "input"))
      (node (ref "C15") (pin "2") (pinfunction "2_2") (pintype "unspecified"))
      (node (ref "C16") (pin "1") (pinfunction "1_1") (pintype "unspecified"))
      (node (ref "J1") (pin "1") (pinfunction "1_1") (pintype "unspecified"))
      (node (ref "Q5") (pin "3") (pinfunction "S_3") (pintype "unspecified"))
      (node (ref "Q6") (pin "2") (pinfunction "D_2") (pintype "unspecified"))
      (node (ref "U3") (pin "5") (pinfunction "VS_5") (pintype "unspecified"))
    )
    (net (code "42") (name "unconnected-(H_Q1-Pad1)") (class "Default")
      (node (ref "H_Q1") (pin "1") (pinfunction "1_1") (pintype "unspecified+no_connect"))
    )
    (net (code "43") (name "unconnected-(H_Q2-Pad1)") (class "Default")
      (node (ref "H_Q2") (pin "1") (pinfunction "1_1") (pintype "unspecified+no_connect"))
    )
    (net (code "44") (name "unconnected-(H_Q3-Pad1)") (class "Default")
      (node (ref "H_Q3") (pin "1") (pinfunction "1_1") (pintype "unspecified"))
    )
    (net (code "45") (name "unconnected-(H_Q4-Pad1)") (class "Default")
      (node (ref "H_Q4") (pin "1") (pinfunction "1_1") (pintype "unspecified+no_connect"))
    )
    (net (code "46") (name "unconnected-(H_Q5-Pad1)") (class "Default")
      (node (ref "H_Q5") (pin "1") (pinfunction "1_1") (pintype "unspecified+no_connect"))
    )
    (net (code "47") (name "unconnected-(H_Q6-Pad1)") (class "Default")
      (node (ref "H_Q6") (pin "1") (pinfunction "1_1") (pintype "unspecified+no_connect"))
    )
    (net (code "48") (name "unconnected-(STM32-PA0-Pad25)") (class "Default")
      (node (ref "STM32") (pin "25") (pinfunction "PA0_25") (pintype "unspecified"))
    )
    (net (code "49") (name "unconnected-(STM32-PA1-Pad26)") (class "Default")
      (node (ref "STM32") (pin "26") (pinfunction "PA1_26") (pintype "unspecified"))
    )
    (net (code "50") (name "unconnected-(STM32-PA2-Pad27)") (class "Default")
      (node (ref "STM32") (pin "27") (pinfunction "PA2_27") (pintype "unspecified"))
    )
    (net (code "51") (name "unconnected-(STM32-PA3-Pad28)") (class "Default")
      (node (ref "STM32") (pin "28") (pinfunction "PA3_28") (pintype "unspecified"))
    )
    (net (code "52") (name "unconnected-(STM32-PA4-Pad29)") (class "Default")
      (node (ref "STM32") (pin "29") (pinfunction "PA4_29") (pintype "unspecified"))
    )
    (net (code "53") (name "unconnected-(STM32-PA5-Pad30)") (class "Default")
      (node (ref "STM32") (pin "30") (pinfunction "PA5_30") (pintype "unspecified"))
    )
    (net (code "54") (name "unconnected-(STM32-PA6-Pad31)") (class "Default")
      (node (ref "STM32") (pin "31") (pinfunction "PA6_31") (pintype "unspecified"))
    )
    (net (code "55") (name "unconnected-(STM32-PA7-Pad32)") (class "Default")
      (node (ref "STM32") (pin "32") (pinfunction "PA7_32") (pintype "unspecified"))
    )
    (net (code "56") (name "unconnected-(STM32-PA12-Pad9)") (class "Default")
      (node (ref "STM32") (pin "9") (pinfunction "PA12_9") (pintype "unspecified"))
    )
    (net (code "57") (name "unconnected-(STM32-PA15-Pad10)") (class "Default")
      (node (ref "STM32") (pin "10") (pinfunction "PA15_10") (pintype "unspecified"))
    )
    (net (code "58") (name "unconnected-(STM32-PB0-Pad33)") (class "Default")
      (node (ref "STM32") (pin "33") (pinfunction "PB0_33") (pintype "unspecified"))
    )
    (net (code "59") (name "unconnected-(STM32-PB1-Pad34)") (class "Default")
      (node (ref "STM32") (pin "34") (pinfunction "PB1_34") (pintype "unspecified"))
    )
    (net (code "60") (name "unconnected-(STM32-PB3-Pad11)") (class "Default")
      (node (ref "STM32") (pin "11") (pinfunction "PB3_11") (pintype "unspecified"))
    )
    (net (code "61") (name "unconnected-(STM32-PB4-Pad12)") (class "Default")
      (node (ref "STM32") (pin "12") (pinfunction "PB4_12") (pintype "unspecified"))
    )
    (net (code "62") (name "unconnected-(STM32-PB5-Pad13)") (class "Default")
      (node (ref "STM32") (pin "13") (pinfunction "PB5_13") (pintype "unspecified"))
    )
    (net (code "63") (name "unconnected-(STM32-PB6-Pad14)") (class "Default")
      (node (ref "STM32") (pin "14") (pinfunction "PB6_14") (pintype "unspecified"))
    )
    (net (code "64") (name "unconnected-(STM32-PB7-Pad15)") (class "Default")
      (node (ref "STM32") (pin "15") (pinfunction "PB7_15") (pintype "unspecified"))
    )
    (net (code "65") (name "unconnected-(STM32-PB8-Pad16)") (class "Default")
      (node (ref "STM32") (pin "16") (pinfunction "PB8_16") (pintype "unspecified"))
    )
    (net (code "66") (name "unconnected-(STM32-PB9-Pad17)") (class "Default")
      (node (ref "STM32") (pin "17") (pinfunction "PB9_17") (pintype "unspecified"))
    )
    (net (code "67") (name "unconnected-(STM32-PB10-Pad35)") (class "Default")
      (node (ref "STM32") (pin "35") (pinfunction "PB10_35") (pintype "unspecified"))
    )
    (net (code "68") (name "unconnected-(STM32-PB11-Pad36)") (class "Default")
      (node (ref "STM32") (pin "36") (pinfunction "PB11_36") (pintype "unspecified"))
    )
    (net (code "69") (name "unconnected-(STM32-PB12-Pad1)") (class "Default")
      (node (ref "STM32") (pin "1") (pinfunction "PB12_1") (pintype "unspecified"))
    )
    (net (code "70") (name "unconnected-(STM32-PC13-Pad22)") (class "Default")
      (node (ref "STM32") (pin "22") (pinfunction "PC13_22") (pintype "unspecified"))
    )
    (net (code "71") (name "unconnected-(STM32-PC14-Pad23)") (class "Default")
      (node (ref "STM32") (pin "23") (pinfunction "PC14_23") (pintype "unspecified"))
    )
    (net (code "72") (name "unconnected-(STM32-PC15-Pad24)") (class "Default")
      (node (ref "STM32") (pin "24") (pinfunction "PC15_24") (pintype "unspecified"))
    )
    (net (code "73") (name "unconnected-(STM32-RST-Pad37)") (class "Default")
      (node (ref "STM32") (pin "37") (pinfunction "RST_37") (pintype "unspecified"))
    )
    (net (code "74") (name "unconnected-(STM32-VBAT-Pad21)") (class "Default")
      (node (ref "STM32") (pin "21") (pinfunction "VBAT_21") (pintype "unspecified"))
    )
    (net (code "75") (name "unconnected-(U1-NC-Pad4)") (class "Default")
      (node (ref "U1") (pin "4") (pinfunction "NC_4") (pintype "unspecified+no_connect"))
    )
    (net (code "76") (name "unconnected-(U1-NC-Pad8)") (class "Default")
      (node (ref "U1") (pin "8") (pinfunction "NC_8") (pintype "unspecified+no_connect"))
    )
    (net (code "77") (name "unconnected-(U1-NC-Pad14)") (class "Default")
      (node (ref "U1") (pin "14") (pinfunction "NC_14") (pintype "unspecified+no_connect"))
    )
    (net (code "78") (name "unconnected-(U2-NC-Pad4)") (class "Default")
      (node (ref "U2") (pin "4") (pinfunction "NC_4") (pintype "unspecified+no_connect"))
    )
    (net (code "79") (name "unconnected-(U2-NC-Pad8)") (class "Default")
      (node (ref "U2") (pin "8") (pinfunction "NC_8") (pintype "unspecified+no_connect"))
    )
    (net (code "80") (name "unconnected-(U2-NC-Pad14)") (class "Default")
      (node (ref "U2") (pin "14") (pinfunction "NC_14") (pintype "unspecified+no_connect"))
    )
    (net (code "81") (name "unconnected-(U3-NC-Pad4)") (class "Default")
      (node (ref "U3") (pin "4") (pinfunction "NC_4") (pintype "unspecified+no_connect"))
    )
    (net (code "82") (name "unconnected-(U3-NC-Pad8)") (class "Default")
      (node (ref "U3") (pin "8") (pinfunction "NC_8") (pintype "unspecified+no_connect"))
    )
    (net (code "83") (name "unconnected-(U3-NC-Pad14)") (class "Default")
      (node (ref "U3") (pin "14") (pinfunction "NC_14") (pintype "unspecified+no_connect"))
    )
  )
)
